# cdf-teensy-interrupter-v3.net
KiCad netlist of a schematic drawn in EAGLE
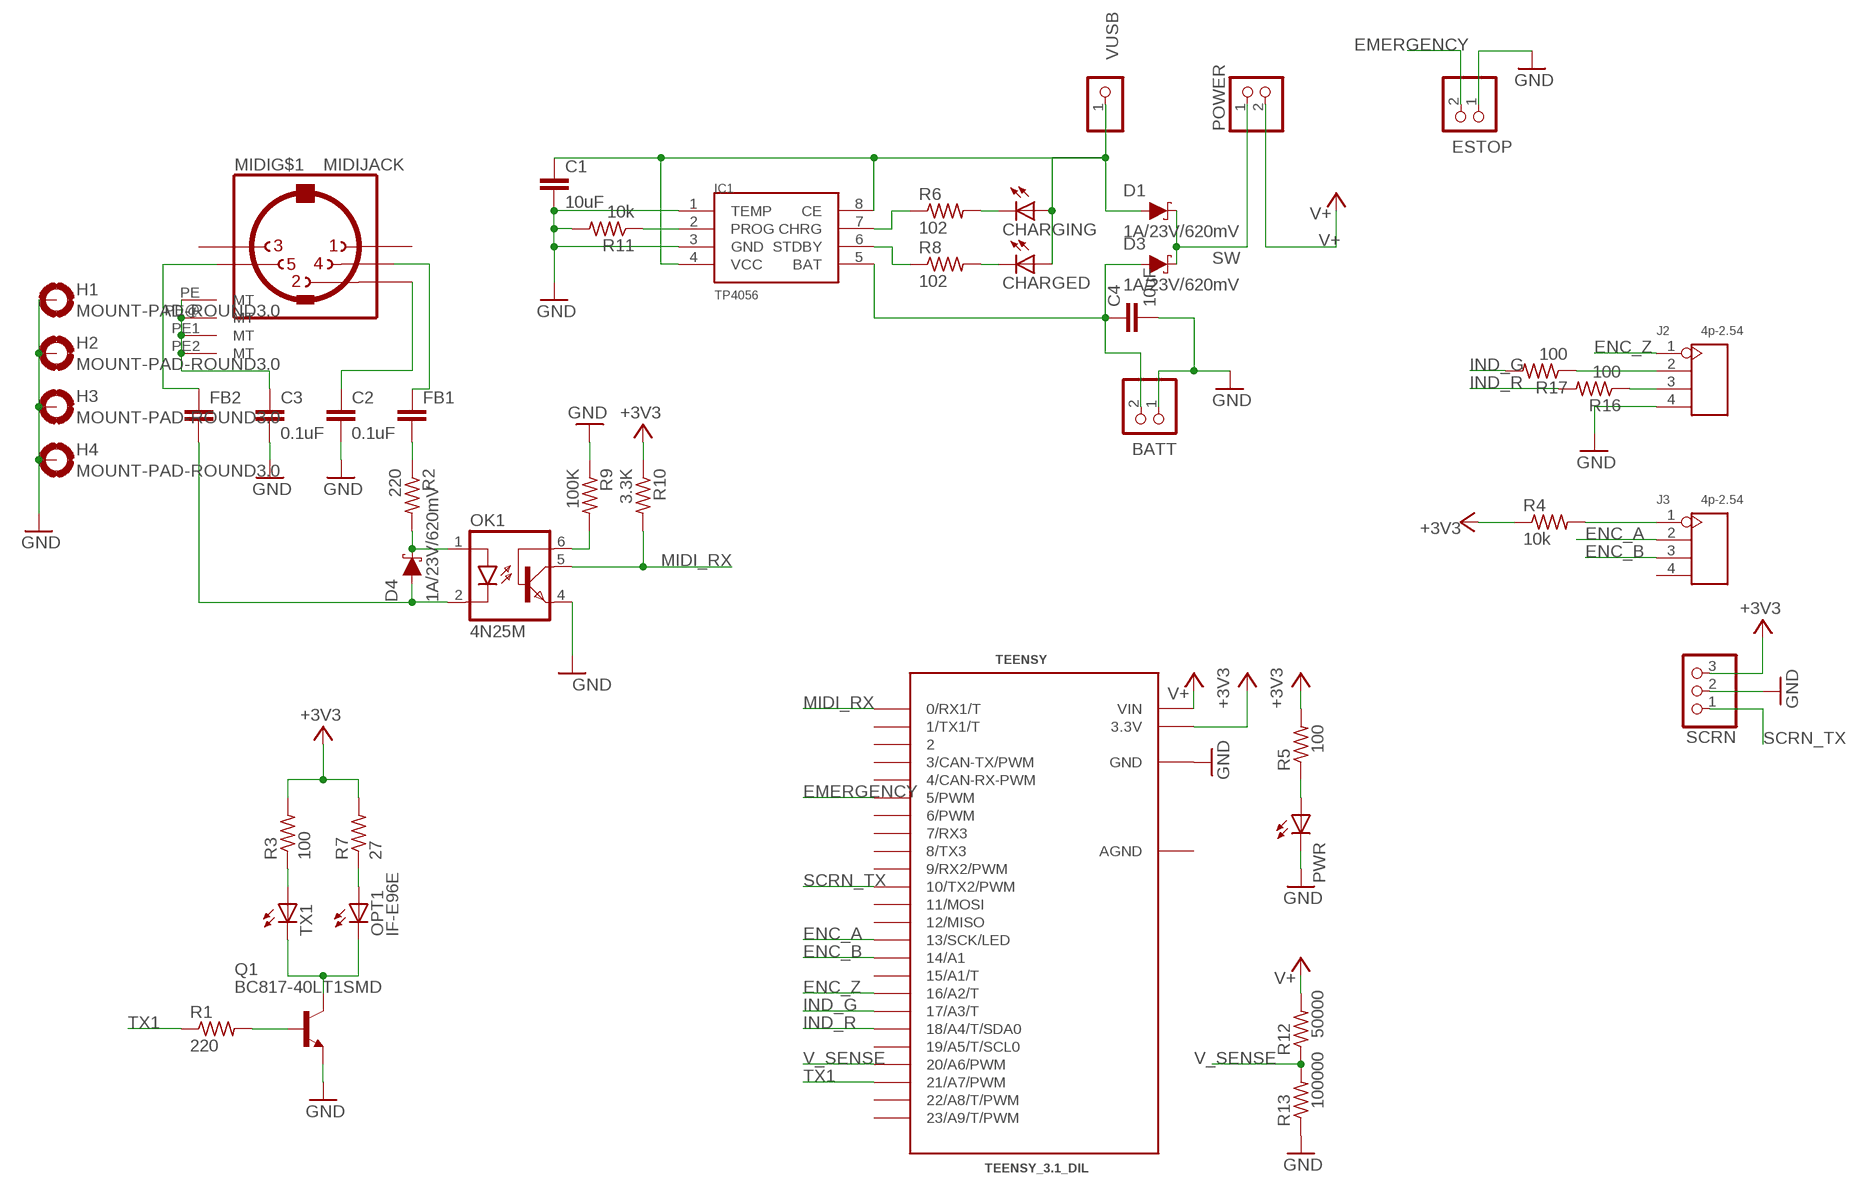
[diagram p0: schematic, sheet 1]

(export (version "E")
  (design (tool "Eeschema 10.0.6"))
  (components
    (comp (ref "BATT")
      (value "PINHD-1X2")
      (footprint "eagle-import:1X02")
      (libsource (lib "eagle-import") (part "PINHD-1X2"))
    )
    (comp (ref "C1")
      (value "10uF")
      (footprint "eagle-import:C0805")
      (libsource (lib "eagle-import") (part "C-EUC0805"))
    )
    (comp (ref "C2")
      (value "0.1uF")
      (footprint "eagle-import:C0805")
      (libsource (lib "eagle-import") (part "C-EUC0805"))
    )
    (comp (ref "C3")
      (value "0.1uF")
      (footprint "eagle-import:C0805")
      (libsource (lib "eagle-import") (part "C-EUC0805"))
    )
    (comp (ref "C4")
      (value "10uF")
      (footprint "eagle-import:C0805")
      (libsource (lib "eagle-import") (part "C-EUC0805"))
    )
    (comp (ref "CHARGED")
      (value "LEDCHIP-LED0805")
      (footprint "eagle-import:CHIP-LED0805")
      (libsource (lib "eagle-import") (part "LEDCHIP-LED0805"))
    )
    (comp (ref "CHARGING")
      (value "LEDCHIP-LED0805")
      (footprint "eagle-import:CHIP-LED0805")
      (libsource (lib "eagle-import") (part "LEDCHIP-LED0805"))
    )
    (comp (ref "D1")
      (value "1A/23V/620mV")
      (footprint "eagle-import:SOD-323")
      (libsource (lib "eagle-import") (part "DIODE-SCHOTTKY-BAT20J"))
    )
    (comp (ref "D3")
      (value "1A/23V/620mV")
      (footprint "eagle-import:SOD-323")
      (libsource (lib "eagle-import") (part "DIODE-SCHOTTKY-BAT20J"))
    )
    (comp (ref "D4")
      (value "1A/23V/620mV")
      (footprint "eagle-import:SOD-323")
      (libsource (lib "eagle-import") (part "DIODE-SCHOTTKY-BAT20J"))
    )
    (comp (ref "ESTOP")
      (value "PINHD-1X2")
      (footprint "eagle-import:1X02")
      (libsource (lib "eagle-import") (part "PINHD-1X2"))
    )
    (comp (ref "FB1")
      (value "C-EUC0805")
      (footprint "eagle-import:C0805")
      (libsource (lib "eagle-import") (part "C-EUC0805"))
    )
    (comp (ref "FB2")
      (value "C-EUC0805")
      (footprint "eagle-import:C0805")
      (libsource (lib "eagle-import") (part "C-EUC0805"))
    )
    (comp (ref "H1")
      (value "MOUNT-PAD-ROUND3.0")
      (footprint "eagle-import:3,0-PAD")
      (libsource (lib "eagle-import") (part "MOUNT-PAD-ROUND3.0"))
    )
    (comp (ref "H2")
      (value "MOUNT-PAD-ROUND3.0")
      (footprint "eagle-import:3,0-PAD")
      (libsource (lib "eagle-import") (part "MOUNT-PAD-ROUND3.0"))
    )
    (comp (ref "H3")
      (value "MOUNT-PAD-ROUND3.0")
      (footprint "eagle-import:3,0-PAD")
      (libsource (lib "eagle-import") (part "MOUNT-PAD-ROUND3.0"))
    )
    (comp (ref "H4")
      (value "MOUNT-PAD-ROUND3.0")
      (footprint "eagle-import:3,0-PAD")
      (libsource (lib "eagle-import") (part "MOUNT-PAD-ROUND3.0"))
    )
    (comp (ref "IC1")
      (value "TP4056")
      (footprint "eagle-import:SOP-8")
      (libsource (lib "eagle-import") (part "TP4056"))
    )
    (comp (ref "J2")
      (value "4p-2.54")
      (footprint "eagle-import:H4-2.54")
      (fields (field (name "MPN") "P125-1104A0BS116A1"))
      (libsource (lib "eagle-import") (part "DIP-BLACK-MALE-HEADER-VERT(4P-2.54)"))
    )
    (comp (ref "J3")
      (value "4p-2.54")
      (footprint "eagle-import:H4-2.54")
      (fields (field (name "MPN") "P125-1104A0BS116A1"))
      (libsource (lib "eagle-import") (part "DIP-BLACK-MALE-HEADER-VERT(4P-2.54)"))
    )
    (comp (ref "MIDI")
      (value "MIDIJACK")
      (footprint "eagle-import:CP-2350")
      (libsource (lib "eagle-import") (part "MIDIJACK"))
    )
    (comp (ref "OK1")
      (value "4N25M")
      (footprint "eagle-import:DIL06")
      (fields (field (name "MPN") "4N25-M"))
      (libsource (lib "eagle-import") (part "4N?M25"))
    )
    (comp (ref "OPT1")
      (value "IF-E96E")
      (footprint "eagle-import:IF-E96E")
      (libsource (lib "eagle-import") (part "IF-E96E"))
    )
    (comp (ref "POWER")
      (value "PINHD-1X2")
      (footprint "eagle-import:1X02")
      (libsource (lib "eagle-import") (part "PINHD-1X2"))
    )
    (comp (ref "PWR")
      (value "LEDCHIP-LED0805")
      (footprint "eagle-import:CHIP-LED0805")
      (libsource (lib "eagle-import") (part "LEDCHIP-LED0805"))
    )
    (comp (ref "Q1")
      (value "BC817-40LT1SMD")
      (footprint "eagle-import:SOT23-BEC")
      (libsource (lib "eagle-import") (part "BC817SMD-40LT1"))
    )
    (comp (ref "R1")
      (value "220")
      (footprint "eagle-import:R0805")
      (libsource (lib "eagle-import") (part "R-US_R0805"))
    )
    (comp (ref "R2")
      (value "220")
      (footprint "eagle-import:R0805")
      (libsource (lib "eagle-import") (part "R-US_R0805"))
    )
    (comp (ref "R3")
      (value "100")
      (footprint "eagle-import:R0805")
      (libsource (lib "eagle-import") (part "R-US_R0805"))
    )
    (comp (ref "R4")
      (value "10k")
      (footprint "eagle-import:R0805")
      (libsource (lib "eagle-import") (part "R-US_R0805"))
    )
    (comp (ref "R5")
      (value "100")
      (footprint "eagle-import:R0805")
      (libsource (lib "eagle-import") (part "R-US_R0805"))
    )
    (comp (ref "R6")
      (value "102")
      (footprint "eagle-import:R0805")
      (libsource (lib "eagle-import") (part "R-US_R0805"))
    )
    (comp (ref "R7")
      (value "27")
      (footprint "eagle-import:R0805")
      (libsource (lib "eagle-import") (part "R-US_R0805"))
    )
    (comp (ref "R8")
      (value "102")
      (footprint "eagle-import:R0805")
      (libsource (lib "eagle-import") (part "R-US_R0805"))
    )
    (comp (ref "R9")
      (value "100K")
      (footprint "eagle-import:R0805")
      (libsource (lib "eagle-import") (part "R-US_R0805"))
    )
    (comp (ref "R10")
      (value "3.3K")
      (footprint "eagle-import:R0805")
      (libsource (lib "eagle-import") (part "R-US_R0805"))
    )
    (comp (ref "R11")
      (value "10k")
      (footprint "eagle-import:R0805")
      (libsource (lib "eagle-import") (part "R-US_R0805"))
    )
    (comp (ref "R12")
      (value "50000")
      (footprint "eagle-import:R0805")
      (libsource (lib "eagle-import") (part "R-US_R0805"))
    )
    (comp (ref "R13")
      (value "100000")
      (footprint "eagle-import:R0805")
      (libsource (lib "eagle-import") (part "R-US_R0805"))
    )
    (comp (ref "R16")
      (value "100")
      (footprint "eagle-import:R0805")
      (libsource (lib "eagle-import") (part "R-US_R0805"))
    )
    (comp (ref "R17")
      (value "100")
      (footprint "eagle-import:R0805")
      (libsource (lib "eagle-import") (part "R-US_R0805"))
    )
    (comp (ref "SCRN")
      (value "PINHD-1X3")
      (footprint "eagle-import:1X03")
      (libsource (lib "eagle-import") (part "PINHD-1X3"))
    )
    (comp (ref "TEENSY")
      (value "TEENSY_3.1_DIL")
      (footprint "eagle-import:TEENSY3-DIL")
      (libsource (lib "eagle-import") (part "TEENSY_3.1_DIL"))
    )
    (comp (ref "TX1")
      (value "LEDCHIP-LED0805")
      (footprint "eagle-import:CHIP-LED0805")
      (libsource (lib "eagle-import") (part "LEDCHIP-LED0805"))
    )
    (comp (ref "VUSB")
      (value "PINHD-1X1")
      (footprint "eagle-import:1X01")
      (libsource (lib "eagle-import") (part "PINHD-1X1"))
    )
  )
  (nets
    (net (code "1") (name "+3V3") (class "Default")
      (node (ref "R10") (pin "1") (pinfunction "1_1") (pintype "passive"))
      (node (ref "R3") (pin "2") (pinfunction "2_2") (pintype "passive"))
      (node (ref "R4") (pin "1") (pinfunction "1_1") (pintype "passive"))
      (node (ref "R5") (pin "2") (pinfunction "2_2") (pintype "passive"))
      (node (ref "R7") (pin "2") (pinfunction "2_2") (pintype "passive"))
      (node (ref "SCRN") (pin "3") (pinfunction "3_3") (pintype "passive"))
      (node (ref "TEENSY") (pin "3.3V") (pinfunction "3.3V_3.3V") (pintype "power_in"))
    )
    (net (code "2") (name "/AGND") (class "Default")
      (node (ref "TEENSY") (pin "AGND") (pinfunction "AGND_AGND") (pintype "power_in"))
    )
    (net (code "3") (name "/EMERGENCY") (class "Default")
      (node (ref "ESTOP") (pin "2") (pinfunction "2_2") (pintype "passive"))
      (node (ref "TEENSY") (pin "5") (pinfunction "5/PWM_5") (pintype "bidirectional"))
    )
    (net (code "4") (name "/ENC_A") (class "Default")
      (node (ref "J3") (pin "2") (pinfunction "P$2_2") (pintype "bidirectional"))
      (node (ref "TEENSY") (pin "13") (pinfunction "13/SCK/LED_13") (pintype "bidirectional"))
    )
    (net (code "5") (name "/ENC_B") (class "Default")
      (node (ref "J3") (pin "3") (pinfunction "P$3_3") (pintype "bidirectional"))
      (node (ref "TEENSY") (pin "14/A0") (pinfunction "14/A1_14/A0") (pintype "bidirectional"))
    )
    (net (code "6") (name "/ENC_Z") (class "Default")
      (node (ref "J2") (pin "1") (pinfunction "P$1_1") (pintype "bidirectional"))
      (node (ref "TEENSY") (pin "16/A2") (pinfunction "16/A2/T_16/A2") (pintype "bidirectional"))
    )
    (net (code "7") (name "/IND_G") (class "Default")
      (node (ref "R17") (pin "2") (pinfunction "2_2") (pintype "passive"))
      (node (ref "TEENSY") (pin "17/A3") (pinfunction "17/A3/T_17/A3") (pintype "bidirectional"))
    )
    (net (code "8") (name "/IND_R") (class "Default")
      (node (ref "R16") (pin "2") (pinfunction "2_2") (pintype "passive"))
      (node (ref "TEENSY") (pin "18/A4") (pinfunction "18/A4/T/SDA0_18/A4") (pintype "bidirectional"))
    )
    (net (code "9") (name "/MIDI_RX") (class "Default")
      (node (ref "OK1") (pin "5") (pinfunction "COL_5") (pintype "passive"))
      (node (ref "R10") (pin "2") (pinfunction "2_2") (pintype "passive"))
      (node (ref "TEENSY") (pin "0") (pinfunction "0/RX1/T_0") (pintype "bidirectional"))
    )
    (net (code "10") (name "/SCRN_TX") (class "Default")
      (node (ref "SCRN") (pin "1") (pinfunction "1_1") (pintype "passive"))
      (node (ref "TEENSY") (pin "10") (pinfunction "10/TX2/PWM_10") (pintype "bidirectional"))
    )
    (net (code "11") (name "/SW") (class "Default")
      (node (ref "D1") (pin "C") (pinfunction "C_C") (pintype "passive"))
      (node (ref "D3") (pin "C") (pinfunction "C_C") (pintype "passive"))
      (node (ref "POWER") (pin "1") (pinfunction "1_1") (pintype "passive"))
    )
    (net (code "12") (name "/TX1") (class "Default")
      (node (ref "R1") (pin "1") (pinfunction "1_1") (pintype "passive"))
      (node (ref "TEENSY") (pin "21/A7") (pinfunction "21/A7/PWM_21/A7") (pintype "bidirectional"))
    )
    (net (code "13") (name "/V_SENSE") (class "Default")
      (node (ref "R12") (pin "1") (pinfunction "1_1") (pintype "passive"))
      (node (ref "R13") (pin "2") (pinfunction "2_2") (pintype "passive"))
      (node (ref "TEENSY") (pin "20/A6") (pinfunction "20/A6/PWM_20/A6") (pintype "bidirectional"))
    )
    (net (code "14") (name "GND") (class "Default")
      (node (ref "BATT") (pin "1") (pinfunction "1_1") (pintype "passive"))
      (node (ref "C1") (pin "2") (pinfunction "2_2") (pintype "passive"))
      (node (ref "C2") (pin "2") (pinfunction "2_2") (pintype "passive"))
      (node (ref "C3") (pin "2") (pinfunction "2_2") (pintype "passive"))
      (node (ref "C4") (pin "2") (pinfunction "2_2") (pintype "passive"))
      (node (ref "ESTOP") (pin "1") (pinfunction "1_1") (pintype "passive"))
      (node (ref "H1") (pin "B3,0") (pinfunction "MOUNT_B3,0") (pintype "passive"))
      (node (ref "H2") (pin "B3,0") (pinfunction "MOUNT_B3,0") (pintype "passive"))
      (node (ref "H3") (pin "B3,0") (pinfunction "MOUNT_B3,0") (pintype "passive"))
      (node (ref "H4") (pin "B3,0") (pinfunction "MOUNT_B3,0") (pintype "passive"))
      (node (ref "IC1") (pin "1") (pinfunction "TEMP_1") (pintype "bidirectional"))
      (node (ref "IC1") (pin "3") (pinfunction "GND_3") (pintype "bidirectional"))
      (node (ref "J2") (pin "4") (pinfunction "P$4_4") (pintype "bidirectional"))
      (node (ref "OK1") (pin "4") (pinfunction "EMI_4") (pintype "passive"))
      (node (ref "PWR") (pin "C") (pinfunction "C_C") (pintype "passive"))
      (node (ref "Q1") (pin "E") (pinfunction "E_E") (pintype "passive"))
      (node (ref "R11") (pin "2") (pinfunction "2_2") (pintype "passive"))
      (node (ref "R13") (pin "1") (pinfunction "1_1") (pintype "passive"))
      (node (ref "R9") (pin "1") (pinfunction "1_1") (pintype "passive"))
      (node (ref "SCRN") (pin "2") (pinfunction "2_2") (pintype "passive"))
      (node (ref "TEENSY") (pin "GND") (pinfunction "GND_GND") (pintype "power_in"))
    )
    (net (code "15") (name "Net-(C2-Pad1)") (class "Default")
      (node (ref "C2") (pin "1") (pinfunction "1_1") (pintype "passive"))
      (node (ref "MIDI") (pin "2") (pinfunction "2_2") (pintype "passive"))
    )
    (net (code "16") (name "Net-(CHARGED-PadC)") (class "Default")
      (node (ref "CHARGED") (pin "C") (pinfunction "C_C") (pintype "passive"))
      (node (ref "R8") (pin "2") (pinfunction "2_2") (pintype "passive"))
    )
    (net (code "17") (name "Net-(CHARGING-PadC)") (class "Default")
      (node (ref "CHARGING") (pin "C") (pinfunction "C_C") (pintype "passive"))
      (node (ref "R6") (pin "2") (pinfunction "2_2") (pintype "passive"))
    )
    (net (code "18") (name "Net-(FB1-Pad1)") (class "Default")
      (node (ref "FB1") (pin "1") (pinfunction "1_1") (pintype "passive"))
      (node (ref "MIDI") (pin "4") (pinfunction "4_4") (pintype "passive"))
    )
    (net (code "19") (name "Net-(FB1-Pad2)") (class "Default")
      (node (ref "FB1") (pin "2") (pinfunction "2_2") (pintype "passive"))
      (node (ref "R2") (pin "1") (pinfunction "1_1") (pintype "passive"))
    )
    (net (code "20") (name "Net-(FB2-Pad1)") (class "Default")
      (node (ref "FB2") (pin "1") (pinfunction "1_1") (pintype "passive"))
      (node (ref "MIDI") (pin "5") (pinfunction "5_5") (pintype "passive"))
    )
    (net (code "21") (name "Net-(IC1-BAT)") (class "Default")
      (node (ref "BATT") (pin "2") (pinfunction "2_2") (pintype "passive"))
      (node (ref "C4") (pin "1") (pinfunction "1_1") (pintype "passive"))
      (node (ref "D3") (pin "A") (pinfunction "A_A") (pintype "passive"))
      (node (ref "IC1") (pin "5") (pinfunction "BAT_5") (pintype "bidirectional"))
    )
    (net (code "22") (name "Net-(IC1-CE)") (class "Default")
      (node (ref "C1") (pin "1") (pinfunction "1_1") (pintype "passive"))
      (node (ref "CHARGED") (pin "A") (pinfunction "A_A") (pintype "passive"))
      (node (ref "CHARGING") (pin "A") (pinfunction "A_A") (pintype "passive"))
      (node (ref "D1") (pin "A") (pinfunction "A_A") (pintype "passive"))
      (node (ref "IC1") (pin "4") (pinfunction "VCC_4") (pintype "bidirectional"))
      (node (ref "IC1") (pin "8") (pinfunction "CE_8") (pintype "bidirectional"))
      (node (ref "VUSB") (pin "1") (pinfunction "1_1") (pintype "passive"))
    )
    (net (code "23") (name "Net-(IC1-CHRG)") (class "Default")
      (node (ref "IC1") (pin "7") (pinfunction "CHRG_7") (pintype "bidirectional"))
      (node (ref "R6") (pin "1") (pinfunction "1_1") (pintype "passive"))
    )
    (net (code "24") (name "Net-(IC1-PROG)") (class "Default")
      (node (ref "IC1") (pin "2") (pinfunction "PROG_2") (pintype "bidirectional"))
      (node (ref "R11") (pin "1") (pinfunction "1_1") (pintype "passive"))
    )
    (net (code "25") (name "Net-(IC1-STDBY)") (class "Default")
      (node (ref "IC1") (pin "6") (pinfunction "STDBY_6") (pintype "bidirectional"))
      (node (ref "R8") (pin "1") (pinfunction "1_1") (pintype "passive"))
    )
    (net (code "26") (name "Net-(J2-P$2)") (class "Default")
      (node (ref "J2") (pin "2") (pinfunction "P$2_2") (pintype "bidirectional"))
      (node (ref "R17") (pin "1") (pinfunction "1_1") (pintype "passive"))
    )
    (net (code "27") (name "Net-(J2-P$3)") (class "Default")
      (node (ref "J2") (pin "3") (pinfunction "P$3_3") (pintype "bidirectional"))
      (node (ref "R16") (pin "1") (pinfunction "1_1") (pintype "passive"))
    )
    (net (code "28") (name "Net-(J3-P$1)") (class "Default")
      (node (ref "J3") (pin "1") (pinfunction "P$1_1") (pintype "bidirectional"))
      (node (ref "R4") (pin "2") (pinfunction "2_2") (pintype "passive"))
    )
    (net (code "29") (name "Net-(MIDIB-MT)") (class "Default")
      (node (ref "C3") (pin "1") (pinfunction "1_1") (pintype "passive"))
      (node (ref "MIDI") (pin "PE") (pinfunction "MT_PE") (pintype "passive"))
      (node (ref "MIDI") (pin "PE1") (pinfunction "MT_PE1") (pintype "passive"))
      (node (ref "MIDI") (pin "PE2") (pinfunction "MT_PE2") (pintype "passive"))
      (node (ref "MIDI") (pin "PE@") (pinfunction "MT_PE@") (pintype "passive"))
    )
    (net (code "30") (name "Net-(OK1-A)") (class "Default")
      (node (ref "D4") (pin "C") (pinfunction "C_C") (pintype "passive"))
      (node (ref "OK1") (pin "1") (pinfunction "A_1") (pintype "passive"))
      (node (ref "R2") (pin "2") (pinfunction "2_2") (pintype "passive"))
    )
    (net (code "31") (name "Net-(OK1-BAS)") (class "Default")
      (node (ref "OK1") (pin "6") (pinfunction "BAS_6") (pintype "passive"))
      (node (ref "R9") (pin "2") (pinfunction "2_2") (pintype "passive"))
    )
    (net (code "32") (name "Net-(OK1-C)") (class "Default")
      (node (ref "D4") (pin "A") (pinfunction "A_A") (pintype "passive"))
      (node (ref "FB2") (pin "2") (pinfunction "2_2") (pintype "passive"))
      (node (ref "OK1") (pin "2") (pinfunction "C_2") (pintype "passive"))
    )
    (net (code "33") (name "Net-(OPT1-A)") (class "Default")
      (node (ref "OPT1") (pin "P$2_ANODE+") (pinfunction "A_P$2_ANODE+") (pintype "passive"))
      (node (ref "R7") (pin "1") (pinfunction "1_1") (pintype "passive"))
    )
    (net (code "34") (name "Net-(OPT1-C)") (class "Default")
      (node (ref "OPT1") (pin "P$1_CATHODE-") (pinfunction "C_P$1_CATHODE-") (pintype "passive"))
      (node (ref "Q1") (pin "C") (pinfunction "C_C") (pintype "passive"))
      (node (ref "TX1") (pin "C") (pinfunction "C_C") (pintype "passive"))
    )
    (net (code "35") (name "Net-(PWR-PadA)") (class "Default")
      (node (ref "PWR") (pin "A") (pinfunction "A_A") (pintype "passive"))
      (node (ref "R5") (pin "1") (pinfunction "1_1") (pintype "passive"))
    )
    (net (code "36") (name "Net-(Q1-PadB)") (class "Default")
      (node (ref "Q1") (pin "B") (pinfunction "B_B") (pintype "passive"))
      (node (ref "R1") (pin "2") (pinfunction "2_2") (pintype "passive"))
    )
    (net (code "37") (name "Net-(R3-Pad1)") (class "Default")
      (node (ref "R3") (pin "1") (pinfunction "1_1") (pintype "passive"))
      (node (ref "TX1") (pin "A") (pinfunction "A_A") (pintype "passive"))
    )
    (net (code "38") (name "V+") (class "Default")
      (node (ref "POWER") (pin "2") (pinfunction "2_2") (pintype "passive"))
      (node (ref "R12") (pin "2") (pinfunction "2_2") (pintype "passive"))
      (node (ref "TEENSY") (pin "VIN") (pinfunction "VIN_VIN") (pintype "power_in"))
    )
    (net (code "39") (name "unconnected-(J3-P$4-Pad4)") (class "Default")
      (node (ref "J3") (pin "4") (pinfunction "P$4_4") (pintype "bidirectional"))
    )
    (net (code "40") (name "unconnected-(MIDI-Pad1)") (class "Default")
      (node (ref "MIDI") (pin "1") (pinfunction "1_1") (pintype "passive"))
    )
    (net (code "41") (name "unconnected-(MIDI-Pad3)") (class "Default")
      (node (ref "MIDI") (pin "3") (pinfunction "3_3") (pintype "passive"))
    )
    (net (code "42") (name "unconnected-(TEENSY-1{slash}TX1{slash}T-Pad1)") (class "Default")
      (node (ref "TEENSY") (pin "1") (pinfunction "1/TX1/T_1") (pintype "bidirectional"))
    )
    (net (code "43") (name "unconnected-(TEENSY-3{slash}CAN-TX{slash}PWM-Pad3)") (class "Default")
      (node (ref "TEENSY") (pin "3") (pinfunction "3/CAN-TX/PWM_3") (pintype "bidirectional"))
    )
    (net (code "44") (name "unconnected-(TEENSY-4{slash}CAN-RX-PWM-Pad4)") (class "Default")
      (node (ref "TEENSY") (pin "4") (pinfunction "4/CAN-RX-PWM_4") (pintype "bidirectional"))
    )
    (net (code "45") (name "unconnected-(TEENSY-6{slash}PWM-Pad6)") (class "Default")
      (node (ref "TEENSY") (pin "6") (pinfunction "6/PWM_6") (pintype "bidirectional"))
    )
    (net (code "46") (name "unconnected-(TEENSY-7{slash}RX3-Pad7)") (class "Default")
      (node (ref "TEENSY") (pin "7") (pinfunction "7/RX3_7") (pintype "bidirectional"))
    )
    (net (code "47") (name "unconnected-(TEENSY-8{slash}TX3-Pad8)") (class "Default")
      (node (ref "TEENSY") (pin "8") (pinfunction "8/TX3_8") (pintype "bidirectional"))
    )
    (net (code "48") (name "unconnected-(TEENSY-9{slash}RX2{slash}PWM-Pad9)") (class "Default")
      (node (ref "TEENSY") (pin "9") (pinfunction "9/RX2/PWM_9") (pintype "bidirectional"))
    )
    (net (code "49") (name "unconnected-(TEENSY-11{slash}MOSI-Pad11)") (class "Default")
      (node (ref "TEENSY") (pin "11") (pinfunction "11/MOSI_11") (pintype "bidirectional"))
    )
    (net (code "50") (name "unconnected-(TEENSY-12{slash}MISO-Pad12)") (class "Default")
      (node (ref "TEENSY") (pin "12") (pinfunction "12/MISO_12") (pintype "bidirectional"))
    )
    (net (code "51") (name "unconnected-(TEENSY-15{slash}A1{slash}T-Pad15{slash}A1)") (class "Default")
      (node (ref "TEENSY") (pin "15/A1") (pinfunction "15/A1/T_15/A1") (pintype "bidirectional"))
    )
    (net (code "52") (name "unconnected-(TEENSY-19{slash}A5{slash}T{slash}SCL0-Pad19{slash}A5)") (class "Default")
      (node (ref "TEENSY") (pin "19/A5") (pinfunction "19/A5/T/SCL0_19/A5") (pintype "bidirectional"))
    )
    (net (code "53") (name "unconnected-(TEENSY-22{slash}A8{slash}T{slash}PWM-Pad22{slash}A8)") (class "Default")
      (node (ref "TEENSY") (pin "22/A8") (pinfunction "22/A8/T/PWM_22/A8") (pintype "bidirectional"))
    )
    (net (code "54") (name "unconnected-(TEENSY-23{slash}A9{slash}T{slash}PWM-Pad23{slash}A9)") (class "Default")
      (node (ref "TEENSY") (pin "23/A9") (pinfunction "23/A9/T/PWM_23/A9") (pintype "bidirectional"))
    )
    (net (code "55") (name "unconnected-(TEENSY-Pad2)") (class "Default")
      (node (ref "TEENSY") (pin "2") (pinfunction "2_2") (pintype "bidirectional"))
    )
  )
)
